# kbdctrl.net
KiCad netlist of a schematic drawn in EAGLE
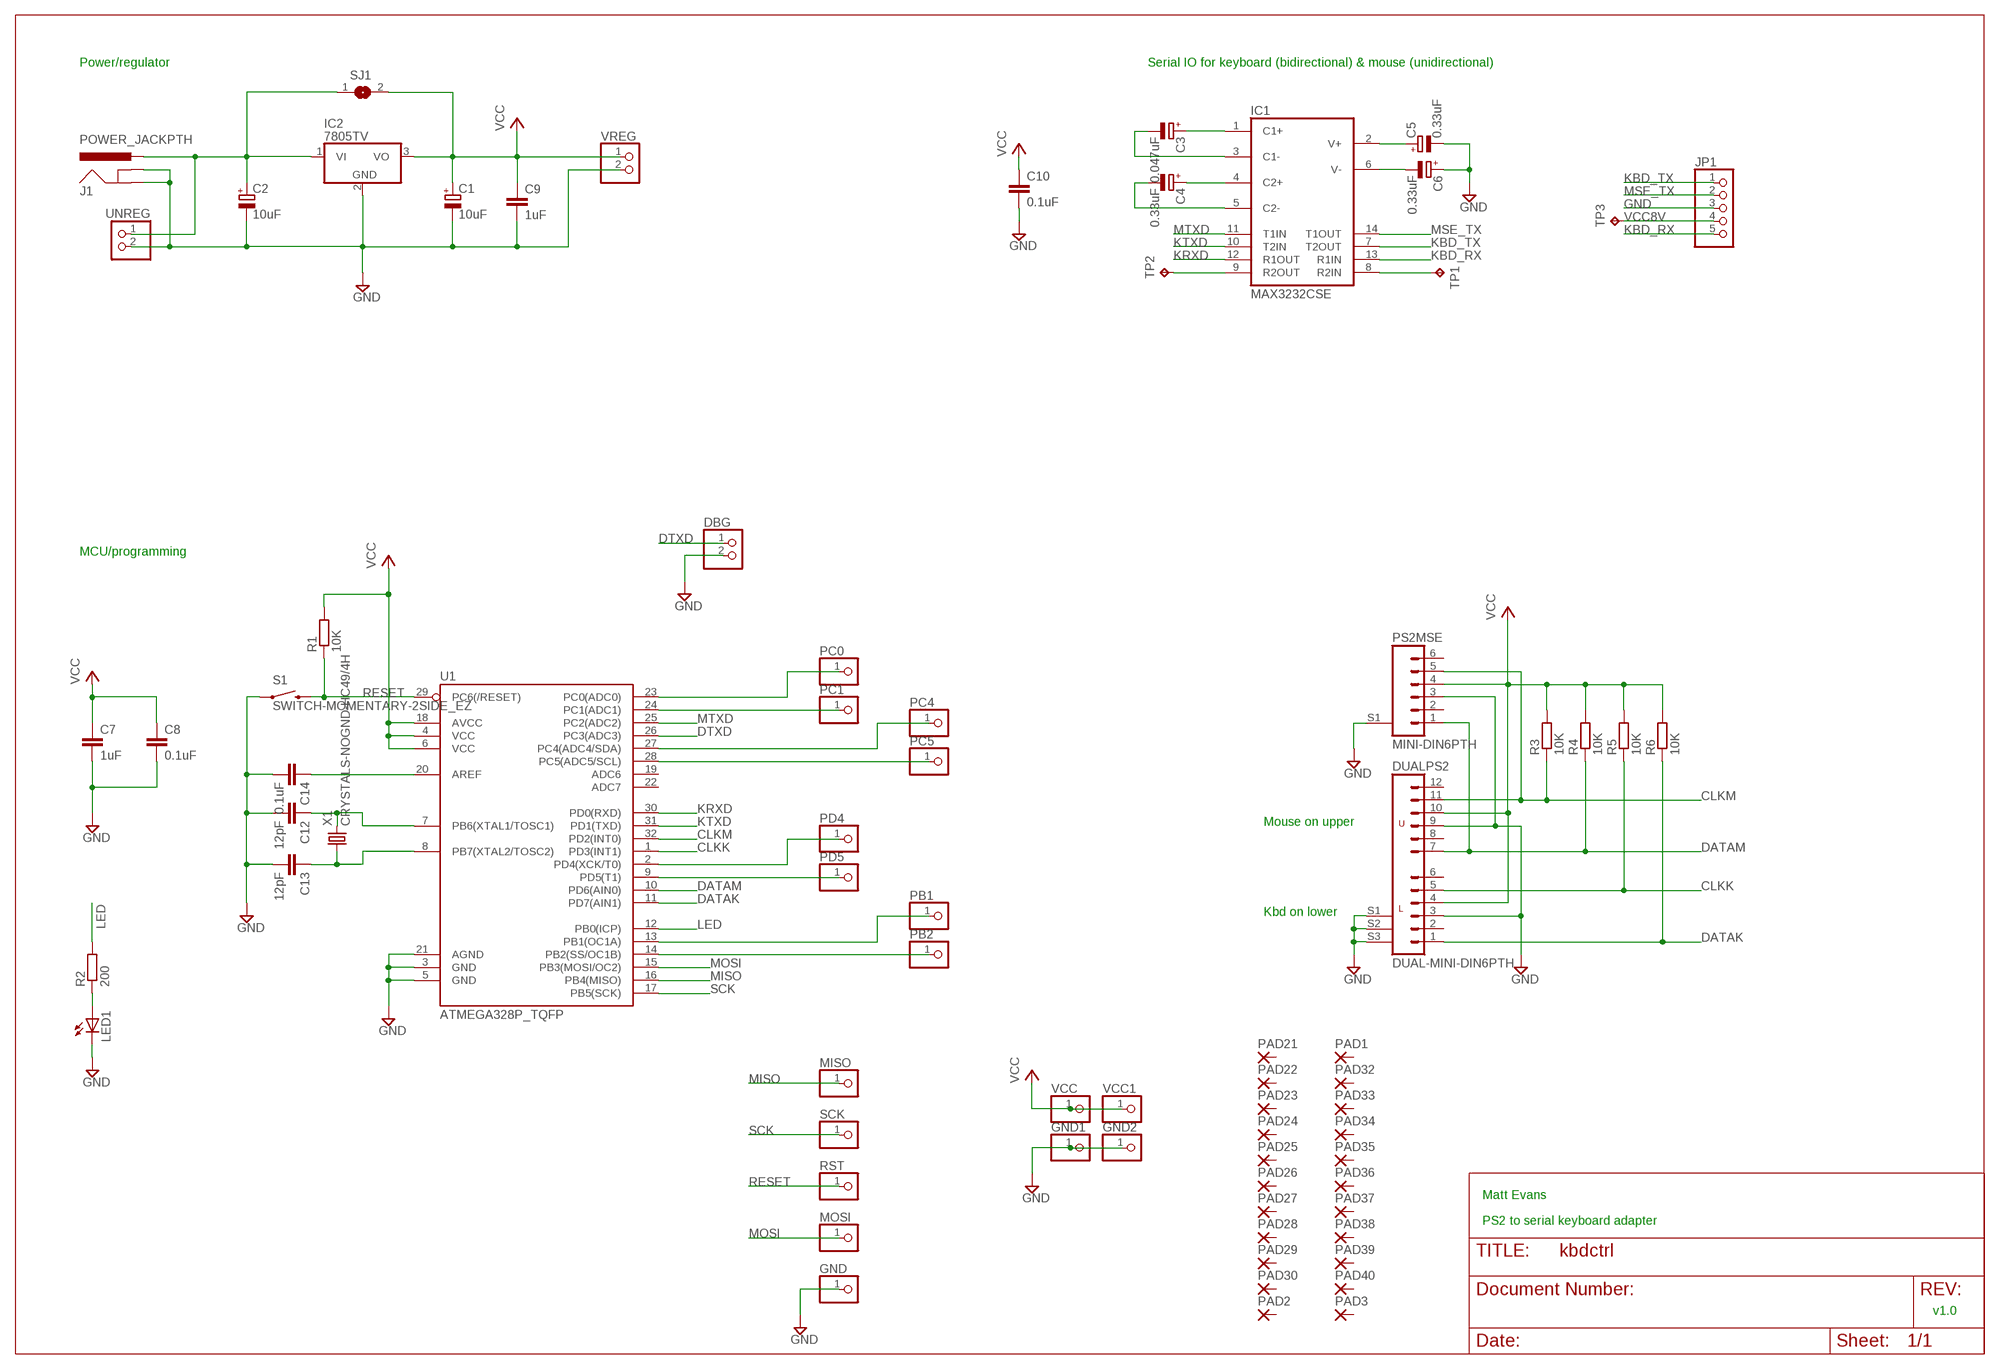
[diagram p0: schematic, sheet 1]

(export (version "E")
  (design (tool "Eeschema 10.0.6"))
  (components
    (comp (ref "C1")
      (value "10uF")
      (footprint "eagle-import:SMC_P")
      (libsource (lib "eagle-import") (part "CPOL-EUSMCP"))
    )
    (comp (ref "C2")
      (value "10uF")
      (footprint "eagle-import:SMC_P")
      (libsource (lib "eagle-import") (part "CPOL-EUSMCP"))
    )
    (comp (ref "C3")
      (value "0.047uF")
      (footprint "eagle-import:SMC_P")
      (libsource (lib "eagle-import") (part "CPOL-EUSMCP"))
    )
    (comp (ref "C4")
      (value "0.33uF")
      (footprint "eagle-import:SMC_P")
      (libsource (lib "eagle-import") (part "CPOL-EUSMCP"))
    )
    (comp (ref "C5")
      (value "0.33uF")
      (footprint "eagle-import:SMC_P")
      (libsource (lib "eagle-import") (part "CPOL-EUSMCP"))
    )
    (comp (ref "C6")
      (value "0.33uF")
      (footprint "eagle-import:SMC_P")
      (libsource (lib "eagle-import") (part "CPOL-EUSMCP"))
    )
    (comp (ref "C7")
      (value "1uF")
      (footprint "eagle-import:C0805")
      (libsource (lib "eagle-import") (part "resistor_C-EUC0805"))
    )
    (comp (ref "C8")
      (value "0.1uF")
      (footprint "eagle-import:C0805")
      (libsource (lib "eagle-import") (part "resistor_C-EUC0805"))
    )
    (comp (ref "C9")
      (value "1uF")
      (footprint "eagle-import:C0805")
      (libsource (lib "eagle-import") (part "resistor_C-EUC0805"))
    )
    (comp (ref "C10")
      (value "0.1uF")
      (footprint "eagle-import:C0805")
      (libsource (lib "eagle-import") (part "resistor_C-EUC0805"))
    )
    (comp (ref "C12")
      (value "12pF")
      (footprint "eagle-import:C0603")
      (libsource (lib "eagle-import") (part "C-EUC0603"))
    )
    (comp (ref "C13")
      (value "12pF")
      (footprint "eagle-import:C0603")
      (libsource (lib "eagle-import") (part "C-EUC0603"))
    )
    (comp (ref "C14")
      (value "0.1uF")
      (footprint "eagle-import:C0603")
      (libsource (lib "eagle-import") (part "C-EUC0603"))
    )
    (comp (ref "DBG")
      (value "PINHD-1X2")
      (footprint "eagle-import:1X02")
      (libsource (lib "eagle-import") (part "PINHD-1X2"))
    )
    (comp (ref "DUALPS2")
      (value "DUAL-MINI-DIN6PTH")
      (footprint "eagle-import:DUAL-MINI-DIN6")
      (libsource (lib "eagle-import") (part "DUAL-MINI-DIN6PTH"))
    )
    (comp (ref "GND")
      (value "PINHD-1X1")
      (footprint "eagle-import:1X01")
      (libsource (lib "eagle-import") (part "PINHD-1X1"))
    )
    (comp (ref "GND1")
      (value "PINHD-1X1")
      (footprint "eagle-import:1X01")
      (libsource (lib "eagle-import") (part "PINHD-1X1"))
    )
    (comp (ref "GND2")
      (value "PINHD-1X1")
      (footprint "eagle-import:1X01")
      (libsource (lib "eagle-import") (part "PINHD-1X1"))
    )
    (comp (ref "IC1")
      (value "MAX3232CSE")
      (footprint "eagle-import:SO16")
      (libsource (lib "eagle-import") (part "MAX3232SEC"))
    )
    (comp (ref "IC2")
      (value "7805TV")
      (footprint "eagle-import:TO220V")
      (libsource (lib "eagle-import") (part "78TV05"))
    )
    (comp (ref "J1")
      (value "POWER_JACKPTH")
      (footprint "eagle-import:POWER_JACK_PTH")
      (libsource (lib "eagle-import") (part "POWER_JACKPTH"))
    )
    (comp (ref "JP1")
      (value "PINHD-1X5")
      (footprint "eagle-import:1X05")
      (libsource (lib "eagle-import") (part "PINHD-1X5"))
    )
    (comp (ref "LED1")
      (value "LEDSML0805")
      (footprint "eagle-import:SML0805")
      (libsource (lib "eagle-import") (part "LEDSML0805"))
    )
    (comp (ref "MISO")
      (value "PINHD-1X1")
      (footprint "eagle-import:1X01")
      (libsource (lib "eagle-import") (part "PINHD-1X1"))
    )
    (comp (ref "MOSI")
      (value "PINHD-1X1")
      (footprint "eagle-import:1X01")
      (libsource (lib "eagle-import") (part "PINHD-1X1"))
    )
    (comp (ref "PAD1")
      (value "1,6/0,9")
      (footprint "eagle-import:1,6_0,9")
      (libsource (lib "eagle-import") (part "1,6/0,9"))
    )
    (comp (ref "PAD2")
      (value "1,6/0,9")
      (footprint "eagle-import:1,6_0,9")
      (libsource (lib "eagle-import") (part "1,6/0,9"))
    )
    (comp (ref "PAD3")
      (value "1,6/0,9")
      (footprint "eagle-import:1,6_0,9")
      (libsource (lib "eagle-import") (part "1,6/0,9"))
    )
    (comp (ref "PAD21")
      (value "1,6/0,9")
      (footprint "eagle-import:1,6_0,9")
      (libsource (lib "eagle-import") (part "1,6/0,9"))
    )
    (comp (ref "PAD22")
      (value "1,6/0,9")
      (footprint "eagle-import:1,6_0,9")
      (libsource (lib "eagle-import") (part "1,6/0,9"))
    )
    (comp (ref "PAD23")
      (value "1,6/0,9")
      (footprint "eagle-import:1,6_0,9")
      (libsource (lib "eagle-import") (part "1,6/0,9"))
    )
    (comp (ref "PAD24")
      (value "1,6/0,9")
      (footprint "eagle-import:1,6_0,9")
      (libsource (lib "eagle-import") (part "1,6/0,9"))
    )
    (comp (ref "PAD25")
      (value "1,6/0,9")
      (footprint "eagle-import:1,6_0,9")
      (libsource (lib "eagle-import") (part "1,6/0,9"))
    )
    (comp (ref "PAD26")
      (value "1,6/0,9")
      (footprint "eagle-import:1,6_0,9")
      (libsource (lib "eagle-import") (part "1,6/0,9"))
    )
    (comp (ref "PAD27")
      (value "1,6/0,9")
      (footprint "eagle-import:1,6_0,9")
      (libsource (lib "eagle-import") (part "1,6/0,9"))
    )
    (comp (ref "PAD28")
      (value "1,6/0,9")
      (footprint "eagle-import:1,6_0,9")
      (libsource (lib "eagle-import") (part "1,6/0,9"))
    )
    (comp (ref "PAD29")
      (value "1,6/0,9")
      (footprint "eagle-import:1,6_0,9")
      (libsource (lib "eagle-import") (part "1,6/0,9"))
    )
    (comp (ref "PAD30")
      (value "1,6/0,9")
      (footprint "eagle-import:1,6_0,9")
      (libsource (lib "eagle-import") (part "1,6/0,9"))
    )
    (comp (ref "PAD32")
      (value "1,6/0,9")
      (footprint "eagle-import:1,6_0,9")
      (libsource (lib "eagle-import") (part "1,6/0,9"))
    )
    (comp (ref "PAD33")
      (value "1,6/0,9")
      (footprint "eagle-import:1,6_0,9")
      (libsource (lib "eagle-import") (part "1,6/0,9"))
    )
    (comp (ref "PAD34")
      (value "1,6/0,9")
      (footprint "eagle-import:1,6_0,9")
      (libsource (lib "eagle-import") (part "1,6/0,9"))
    )
    (comp (ref "PAD35")
      (value "1,6/0,9")
      (footprint "eagle-import:1,6_0,9")
      (libsource (lib "eagle-import") (part "1,6/0,9"))
    )
    (comp (ref "PAD36")
      (value "1,6/0,9")
      (footprint "eagle-import:1,6_0,9")
      (libsource (lib "eagle-import") (part "1,6/0,9"))
    )
    (comp (ref "PAD37")
      (value "1,6/0,9")
      (footprint "eagle-import:1,6_0,9")
      (libsource (lib "eagle-import") (part "1,6/0,9"))
    )
    (comp (ref "PAD38")
      (value "1,6/0,9")
      (footprint "eagle-import:1,6_0,9")
      (libsource (lib "eagle-import") (part "1,6/0,9"))
    )
    (comp (ref "PAD39")
      (value "1,6/0,9")
      (footprint "eagle-import:1,6_0,9")
      (libsource (lib "eagle-import") (part "1,6/0,9"))
    )
    (comp (ref "PAD40")
      (value "1,6/0,9")
      (footprint "eagle-import:1,6_0,9")
      (libsource (lib "eagle-import") (part "1,6/0,9"))
    )
    (comp (ref "PB1")
      (value "PINHD-1X1")
      (footprint "eagle-import:1X01")
      (libsource (lib "eagle-import") (part "PINHD-1X1"))
    )
    (comp (ref "PB2")
      (value "PINHD-1X1")
      (footprint "eagle-import:1X01")
      (libsource (lib "eagle-import") (part "PINHD-1X1"))
    )
    (comp (ref "PC0")
      (value "PINHD-1X1")
      (footprint "eagle-import:1X01")
      (libsource (lib "eagle-import") (part "PINHD-1X1"))
    )
    (comp (ref "PC1")
      (value "PINHD-1X1")
      (footprint "eagle-import:1X01")
      (libsource (lib "eagle-import") (part "PINHD-1X1"))
    )
    (comp (ref "PC4")
      (value "PINHD-1X1")
      (footprint "eagle-import:1X01")
      (libsource (lib "eagle-import") (part "PINHD-1X1"))
    )
    (comp (ref "PC5")
      (value "PINHD-1X1")
      (footprint "eagle-import:1X01")
      (libsource (lib "eagle-import") (part "PINHD-1X1"))
    )
    (comp (ref "PD4")
      (value "PINHD-1X1")
      (footprint "eagle-import:1X01")
      (libsource (lib "eagle-import") (part "PINHD-1X1"))
    )
    (comp (ref "PD5")
      (value "PINHD-1X1")
      (footprint "eagle-import:1X01")
      (libsource (lib "eagle-import") (part "PINHD-1X1"))
    )
    (comp (ref "PS2MSE")
      (value "MINI-DIN6PTH")
      (footprint "eagle-import:MINI-DIN6")
      (libsource (lib "eagle-import") (part "MINI-DIN6PTH"))
    )
    (comp (ref "R1")
      (value "10K")
      (footprint "eagle-import:R0603")
      (libsource (lib "eagle-import") (part "R-EU_R0603"))
    )
    (comp (ref "R2")
      (value "200")
      (footprint "eagle-import:R0603")
      (libsource (lib "eagle-import") (part "R-EU_R0603"))
    )
    (comp (ref "R3")
      (value "10K")
      (footprint "eagle-import:R0603")
      (libsource (lib "eagle-import") (part "R-EU_R0603"))
    )
    (comp (ref "R4")
      (value "10K")
      (footprint "eagle-import:R0603")
      (libsource (lib "eagle-import") (part "R-EU_R0603"))
    )
    (comp (ref "R5")
      (value "10K")
      (footprint "eagle-import:R0603")
      (libsource (lib "eagle-import") (part "R-EU_R0603"))
    )
    (comp (ref "R6")
      (value "10K")
      (footprint "eagle-import:R0603")
      (libsource (lib "eagle-import") (part "R-EU_R0603"))
    )
    (comp (ref "RST")
      (value "PINHD-1X1")
      (footprint "eagle-import:1X01")
      (libsource (lib "eagle-import") (part "PINHD-1X1"))
    )
    (comp (ref "S1")
      (value "SWITCH-MOMENTARY-2SIDE_EZ")
      (footprint "eagle-import:TACTILE-PTH-SIDEEZ")
      (libsource (lib "eagle-import") (part "SWITCH-MOMENTARY-2SIDE_EZ"))
    )
    (comp (ref "SCK")
      (value "PINHD-1X1")
      (footprint "eagle-import:1X01")
      (libsource (lib "eagle-import") (part "PINHD-1X1"))
    )
    (comp (ref "SJ1") (value "SJ") (footprint "eagle-import:SJ") (libsource (lib "eagle-import") (part "SJ")))
    (comp (ref "TP1")
      (value "TPTP09SQ")
      (footprint "eagle-import:TP09SQ")
      (libsource (lib "eagle-import") (part "TPTP09SQ"))
    )
    (comp (ref "TP2")
      (value "TPTP09SQ")
      (footprint "eagle-import:TP09SQ")
      (libsource (lib "eagle-import") (part "TPTP09SQ"))
    )
    (comp (ref "TP3")
      (value "TPTP09SQ")
      (footprint "eagle-import:TP09SQ")
      (libsource (lib "eagle-import") (part "TPTP09SQ"))
    )
    (comp (ref "U1")
      (value "ATMEGA328P_TQFP")
      (footprint "eagle-import:TQFP32-08")
      (libsource (lib "eagle-import") (part "ATMEGA328P_TQFP"))
    )
    (comp (ref "UNREG")
      (value "PINHD-1X2")
      (footprint "eagle-import:1X02")
      (libsource (lib "eagle-import") (part "PINHD-1X2"))
    )
    (comp (ref "VCC")
      (value "PINHD-1X1")
      (footprint "eagle-import:1X01")
      (libsource (lib "eagle-import") (part "PINHD-1X1"))
    )
    (comp (ref "VCC1")
      (value "PINHD-1X1")
      (footprint "eagle-import:1X01")
      (libsource (lib "eagle-import") (part "PINHD-1X1"))
    )
    (comp (ref "VREG")
      (value "PINHD-1X2")
      (footprint "eagle-import:1X02")
      (libsource (lib "eagle-import") (part "PINHD-1X2"))
    )
    (comp (ref "X1")
      (value "CRYSTALS-NOGND-HC49/4H")
      (footprint "eagle-import:HC49")
      (libsource (lib "eagle-import") (part "CRYSTALS-NOGND-HC49/4H"))
    )
  )
  (nets
    (net (code "1") (name "/CLKK") (class "Default")
      (node (ref "DUALPS2") (pin "5") (pinfunction "5_5") (pintype "passive"))
      (node (ref "R5") (pin "1") (pinfunction "1_1") (pintype "passive"))
      (node (ref "U1") (pin "1") (pinfunction "PD3(INT1)_1") (pintype "bidirectional"))
    )
    (net (code "2") (name "/CLKM") (class "Default")
      (node (ref "DUALPS2") (pin "11") (pinfunction "11_11") (pintype "passive"))
      (node (ref "PS2MSE") (pin "5") (pinfunction "5_5") (pintype "passive"))
      (node (ref "R3") (pin "1") (pinfunction "1_1") (pintype "passive"))
      (node (ref "U1") (pin "32") (pinfunction "PD2(INT0)_32") (pintype "bidirectional"))
    )
    (net (code "3") (name "/DATAK") (class "Default")
      (node (ref "DUALPS2") (pin "1") (pinfunction "1_1") (pintype "passive"))
      (node (ref "R6") (pin "1") (pinfunction "1_1") (pintype "passive"))
      (node (ref "U1") (pin "11") (pinfunction "PD7(AIN1)_11") (pintype "bidirectional"))
    )
    (net (code "4") (name "/DATAM") (class "Default")
      (node (ref "DUALPS2") (pin "7") (pinfunction "7_7") (pintype "passive"))
      (node (ref "PS2MSE") (pin "1") (pinfunction "1_1") (pintype "passive"))
      (node (ref "R4") (pin "1") (pinfunction "1_1") (pintype "passive"))
      (node (ref "U1") (pin "10") (pinfunction "PD6(AIN0)_10") (pintype "bidirectional"))
    )
    (net (code "5") (name "/DTXD") (class "Default")
      (node (ref "DBG") (pin "1") (pinfunction "1_1") (pintype "passive"))
      (node (ref "U1") (pin "26") (pinfunction "PC3(ADC3)_26") (pintype "bidirectional"))
    )
    (net (code "6") (name "/KBD_RX") (class "Default")
      (node (ref "IC1") (pin "13") (pinfunction "R1IN_13") (pintype "input"))
      (node (ref "JP1") (pin "5") (pinfunction "5_5") (pintype "passive"))
    )
    (net (code "7") (name "/KBD_TX") (class "Default")
      (node (ref "IC1") (pin "7") (pinfunction "T2OUT_7") (pintype "output"))
      (node (ref "JP1") (pin "1") (pinfunction "1_1") (pintype "passive"))
    )
    (net (code "8") (name "/KRXD") (class "Default")
      (node (ref "IC1") (pin "12") (pinfunction "R1OUT_12") (pintype "output"))
      (node (ref "U1") (pin "30") (pinfunction "PD0(RXD)_30") (pintype "bidirectional"))
    )
    (net (code "9") (name "/KTXD") (class "Default")
      (node (ref "IC1") (pin "10") (pinfunction "T2IN_10") (pintype "input"))
      (node (ref "U1") (pin "31") (pinfunction "PD1(TXD)_31") (pintype "bidirectional"))
    )
    (net (code "10") (name "/LED") (class "Default")
      (node (ref "R2") (pin "2") (pinfunction "2_2") (pintype "passive"))
      (node (ref "U1") (pin "12") (pinfunction "PB0(ICP)_12") (pintype "bidirectional"))
    )
    (net (code "11") (name "/MISO") (class "Default")
      (node (ref "MISO") (pin "1") (pinfunction "1_1") (pintype "passive"))
      (node (ref "U1") (pin "16") (pinfunction "PB4(MISO)_16") (pintype "bidirectional"))
    )
    (net (code "12") (name "/MOSI") (class "Default")
      (node (ref "MOSI") (pin "1") (pinfunction "1_1") (pintype "passive"))
      (node (ref "U1") (pin "15") (pinfunction "PB3(MOSI/OC2)_15") (pintype "bidirectional"))
    )
    (net (code "13") (name "/MSE_TX") (class "Default")
      (node (ref "IC1") (pin "14") (pinfunction "T1OUT_14") (pintype "output"))
      (node (ref "JP1") (pin "2") (pinfunction "2_2") (pintype "passive"))
    )
    (net (code "14") (name "/MTXD") (class "Default")
      (node (ref "IC1") (pin "11") (pinfunction "T1IN_11") (pintype "input"))
      (node (ref "U1") (pin "25") (pinfunction "PC2(ADC2)_25") (pintype "bidirectional"))
    )
    (net (code "15") (name "/RESET") (class "Default")
      (node (ref "R1") (pin "1") (pinfunction "1_1") (pintype "passive"))
      (node (ref "RST") (pin "1") (pinfunction "1_1") (pintype "passive"))
      (node (ref "S1") (pin "2") (pinfunction "2_2") (pintype "passive"))
      (node (ref "U1") (pin "29") (pinfunction "PC6(/RESET)_29") (pintype "bidirectional"))
    )
    (net (code "16") (name "/SCK") (class "Default")
      (node (ref "SCK") (pin "1") (pinfunction "1_1") (pintype "passive"))
      (node (ref "U1") (pin "17") (pinfunction "PB5(SCK)_17") (pintype "bidirectional"))
    )
    (net (code "17") (name "/VCC8V") (class "Default")
      (node (ref "JP1") (pin "4") (pinfunction "4_4") (pintype "passive"))
      (node (ref "TP3") (pin "TP") (pinfunction "TP_TP") (pintype "input"))
    )
    (net (code "18") (name "GND") (class "Default")
      (node (ref "C1") (pin "-") (pinfunction "-_-") (pintype "passive"))
      (node (ref "C10") (pin "2") (pinfunction "2_2") (pintype "passive"))
      (node (ref "C12") (pin "2") (pinfunction "2_2") (pintype "passive"))
      (node (ref "C13") (pin "2") (pinfunction "2_2") (pintype "passive"))
      (node (ref "C14") (pin "2") (pinfunction "2_2") (pintype "passive"))
      (node (ref "C2") (pin "-") (pinfunction "-_-") (pintype "passive"))
      (node (ref "C5") (pin "-") (pinfunction "-_-") (pintype "passive"))
      (node (ref "C6") (pin "+") (pinfunction "+_+") (pintype "passive"))
      (node (ref "C7") (pin "2") (pinfunction "2_2") (pintype "passive"))
      (node (ref "C8") (pin "2") (pinfunction "2_2") (pintype "passive"))
      (node (ref "C9") (pin "2") (pinfunction "2_2") (pintype "passive"))
      (node (ref "DBG") (pin "2") (pinfunction "2_2") (pintype "passive"))
      (node (ref "DUALPS2") (pin "3") (pinfunction "3_3") (pintype "passive"))
      (node (ref "DUALPS2") (pin "9") (pinfunction "9_9") (pintype "passive"))
      (node (ref "DUALPS2") (pin "S1") (pinfunction "P$1_S1") (pintype "passive"))
      (node (ref "DUALPS2") (pin "S2") (pinfunction "P$2_S2") (pintype "passive"))
      (node (ref "DUALPS2") (pin "S3") (pinfunction "P$3_S3") (pintype "passive"))
      (node (ref "GND") (pin "1") (pinfunction "1_1") (pintype "passive"))
      (node (ref "GND1") (pin "1") (pinfunction "1_1") (pintype "passive"))
      (node (ref "GND2") (pin "1") (pinfunction "1_1") (pintype "passive"))
      (node (ref "IC2") (pin "2") (pinfunction "GND_2") (pintype "passive"))
      (node (ref "J1") (pin "GND") (pinfunction "GND_GND") (pintype "bidirectional"))
      (node (ref "J1") (pin "GNDBREAK") (pinfunction "GNDBREAK_GNDBREAK") (pintype "bidirectional"))
      (node (ref "JP1") (pin "3") (pinfunction "3_3") (pintype "passive"))
      (node (ref "LED1") (pin "C") (pinfunction "C_C") (pintype "passive"))
      (node (ref "PS2MSE") (pin "3") (pinfunction "3_3") (pintype "passive"))
      (node (ref "PS2MSE") (pin "S1") (pinfunction "S1_S1") (pintype "passive"))
      (node (ref "S1") (pin "1") (pinfunction "1_1") (pintype "passive"))
      (node (ref "U1") (pin "21") (pinfunction "AGND_21") (pintype "bidirectional"))
      (node (ref "U1") (pin "3") (pinfunction "GND_3") (pintype "bidirectional"))
      (node (ref "U1") (pin "5") (pinfunction "GND_5") (pintype "bidirectional"))
      (node (ref "UNREG") (pin "2") (pinfunction "2_2") (pintype "passive"))
      (node (ref "VREG") (pin "2") (pinfunction "2_2") (pintype "passive"))
    )
    (net (code "19") (name "Net-(IC1A-C1+)") (class "Default")
      (node (ref "C3") (pin "+") (pinfunction "+_+") (pintype "passive"))
      (node (ref "IC1") (pin "1") (pinfunction "C1+_1") (pintype "bidirectional"))
    )
    (net (code "20") (name "Net-(IC1A-C1-)") (class "Default")
      (node (ref "C3") (pin "-") (pinfunction "-_-") (pintype "passive"))
      (node (ref "IC1") (pin "3") (pinfunction "C1-_3") (pintype "bidirectional"))
    )
    (net (code "21") (name "Net-(IC1A-C2+)") (class "Default")
      (node (ref "C4") (pin "+") (pinfunction "+_+") (pintype "passive"))
      (node (ref "IC1") (pin "4") (pinfunction "C2+_4") (pintype "bidirectional"))
    )
    (net (code "22") (name "Net-(IC1A-C2-)") (class "Default")
      (node (ref "C4") (pin "-") (pinfunction "-_-") (pintype "passive"))
      (node (ref "IC1") (pin "5") (pinfunction "C2-_5") (pintype "bidirectional"))
    )
    (net (code "23") (name "Net-(IC1A-R2IN)") (class "Default")
      (node (ref "IC1") (pin "8") (pinfunction "R2IN_8") (pintype "input"))
      (node (ref "TP1") (pin "TP") (pinfunction "TP_TP") (pintype "input"))
    )
    (net (code "24") (name "Net-(IC1A-R2OUT)") (class "Default")
      (node (ref "IC1") (pin "9") (pinfunction "R2OUT_9") (pintype "output"))
      (node (ref "TP2") (pin "TP") (pinfunction "TP_TP") (pintype "input"))
    )
    (net (code "25") (name "Net-(IC1A-V+)") (class "Default")
      (node (ref "C5") (pin "+") (pinfunction "+_+") (pintype "passive"))
      (node (ref "IC1") (pin "2") (pinfunction "V+_2") (pintype "bidirectional"))
    )
    (net (code "26") (name "Net-(IC1A-V-)") (class "Default")
      (node (ref "C6") (pin "-") (pinfunction "-_-") (pintype "passive"))
      (node (ref "IC1") (pin "6") (pinfunction "V-_6") (pintype "bidirectional"))
    )
    (net (code "27") (name "Net-(IC2-VI)") (class "Default")
      (node (ref "C2") (pin "+") (pinfunction "+_+") (pintype "passive"))
      (node (ref "IC2") (pin "1") (pinfunction "VI_1") (pintype "input"))
      (node (ref "J1") (pin "PWR") (pinfunction "PWR_PWR") (pintype "bidirectional"))
      (node (ref "SJ1") (pin "1") (pinfunction "1_1") (pintype "passive"))
      (node (ref "UNREG") (pin "1") (pinfunction "1_1") (pintype "passive"))
    )
    (net (code "28") (name "Net-(LED1-PadA)") (class "Default")
      (node (ref "LED1") (pin "A") (pinfunction "A_A") (pintype "passive"))
      (node (ref "R2") (pin "1") (pinfunction "1_1") (pintype "passive"))
    )
    (net (code "29") (name "Net-(U1-AREF)") (class "Default")
      (node (ref "C14") (pin "1") (pinfunction "1_1") (pintype "passive"))
      (node (ref "U1") (pin "20") (pinfunction "AREF_20") (pintype "bidirectional"))
    )
    (net (code "30") (name "Net-(U1-PB1(OC1A))") (class "Default")
      (node (ref "PB1") (pin "1") (pinfunction "1_1") (pintype "passive"))
      (node (ref "U1") (pin "13") (pinfunction "PB1(OC1A)_13") (pintype "bidirectional"))
    )
    (net (code "31") (name "Net-(U1-PB2(SS{slash}OC1B))") (class "Default")
      (node (ref "PB2") (pin "1") (pinfunction "1_1") (pintype "passive"))
      (node (ref "U1") (pin "14") (pinfunction "PB2(SS/OC1B)_14") (pintype "bidirectional"))
    )
    (net (code "32") (name "Net-(U1-PB6(XTAL1{slash}TOSC1))") (class "Default")
      (node (ref "C12") (pin "1") (pinfunction "1_1") (pintype "passive"))
      (node (ref "U1") (pin "7") (pinfunction "PB6(XTAL1/TOSC1)_7") (pintype "bidirectional"))
      (node (ref "X1") (pin "2") (pinfunction "2_2") (pintype "passive"))
    )
    (net (code "33") (name "Net-(U1-PB7(XTAL2{slash}TOSC2))") (class "Default")
      (node (ref "C13") (pin "1") (pinfunction "1_1") (pintype "passive"))
      (node (ref "U1") (pin "8") (pinfunction "PB7(XTAL2/TOSC2)_8") (pintype "bidirectional"))
      (node (ref "X1") (pin "1") (pinfunction "1_1") (pintype "passive"))
    )
    (net (code "34") (name "Net-(U1-PC0(ADC0))") (class "Default")
      (node (ref "PC0") (pin "1") (pinfunction "1_1") (pintype "passive"))
      (node (ref "U1") (pin "23") (pinfunction "PC0(ADC0)_23") (pintype "bidirectional"))
    )
    (net (code "35") (name "Net-(U1-PC1(ADC1))") (class "Default")
      (node (ref "PC1") (pin "1") (pinfunction "1_1") (pintype "passive"))
      (node (ref "U1") (pin "24") (pinfunction "PC1(ADC1)_24") (pintype "bidirectional"))
    )
    (net (code "36") (name "Net-(U1-PC4(ADC4{slash}SDA))") (class "Default")
      (node (ref "PC4") (pin "1") (pinfunction "1_1") (pintype "passive"))
      (node (ref "U1") (pin "27") (pinfunction "PC4(ADC4/SDA)_27") (pintype "bidirectional"))
    )
    (net (code "37") (name "Net-(U1-PC5(ADC5{slash}SCL))") (class "Default")
      (node (ref "PC5") (pin "1") (pinfunction "1_1") (pintype "passive"))
      (node (ref "U1") (pin "28") (pinfunction "PC5(ADC5/SCL)_28") (pintype "bidirectional"))
    )
    (net (code "38") (name "Net-(U1-PD4(XCK{slash}T0))") (class "Default")
      (node (ref "PD4") (pin "1") (pinfunction "1_1") (pintype "passive"))
      (node (ref "U1") (pin "2") (pinfunction "PD4(XCK/T0)_2") (pintype "bidirectional"))
    )
    (net (code "39") (name "Net-(U1-PD5(T1))") (class "Default")
      (node (ref "PD5") (pin "1") (pinfunction "1_1") (pintype "passive"))
      (node (ref "U1") (pin "9") (pinfunction "PD5(T1)_9") (pintype "bidirectional"))
    )
    (net (code "40") (name "VCC") (class "Default")
      (node (ref "C1") (pin "+") (pinfunction "+_+") (pintype "passive"))
      (node (ref "C10") (pin "1") (pinfunction "1_1") (pintype "passive"))
      (node (ref "C7") (pin "1") (pinfunction "1_1") (pintype "passive"))
      (node (ref "C8") (pin "1") (pinfunction "1_1") (pintype "passive"))
      (node (ref "C9") (pin "1") (pinfunction "1_1") (pintype "passive"))
      (node (ref "DUALPS2") (pin "10") (pinfunction "10_10") (pintype "passive"))
      (node (ref "DUALPS2") (pin "4") (pinfunction "4_4") (pintype "passive"))
      (node (ref "IC2") (pin "3") (pinfunction "VO_3") (pintype "passive"))
      (node (ref "PS2MSE") (pin "4") (pinfunction "4_4") (pintype "passive"))
      (node (ref "R1") (pin "2") (pinfunction "2_2") (pintype "passive"))
      (node (ref "R3") (pin "2") (pinfunction "2_2") (pintype "passive"))
      (node (ref "R4") (pin "2") (pinfunction "2_2") (pintype "passive"))
      (node (ref "R5") (pin "2") (pinfunction "2_2") (pintype "passive"))
      (node (ref "R6") (pin "2") (pinfunction "2_2") (pintype "passive"))
      (node (ref "SJ1") (pin "2") (pinfunction "2_2") (pintype "passive"))
      (node (ref "U1") (pin "18") (pinfunction "AVCC_18") (pintype "bidirectional"))
      (node (ref "U1") (pin "4") (pinfunction "VCC_4") (pintype "bidirectional"))
      (node (ref "U1") (pin "6") (pinfunction "VCC_6") (pintype "bidirectional"))
      (node (ref "VCC") (pin "1") (pinfunction "1_1") (pintype "passive"))
      (node (ref "VCC1") (pin "1") (pinfunction "1_1") (pintype "passive"))
      (node (ref "VREG") (pin "1") (pinfunction "1_1") (pintype "passive"))
    )
    (net (code "41") (name "unconnected-(DUALPS2-Pad2)") (class "Default")
      (node (ref "DUALPS2") (pin "2") (pinfunction "2_2") (pintype "passive"))
    )
    (net (code "42") (name "unconnected-(DUALPS2-Pad6)") (class "Default")
      (node (ref "DUALPS2") (pin "6") (pinfunction "6_6") (pintype "passive"))
    )
    (net (code "43") (name "unconnected-(DUALPS2-Pad8)") (class "Default")
      (node (ref "DUALPS2") (pin "8") (pinfunction "8_8") (pintype "passive"))
    )
    (net (code "44") (name "unconnected-(DUALPS2-Pad12)") (class "Default")
      (node (ref "DUALPS2") (pin "12") (pinfunction "12_12") (pintype "passive"))
    )
    (net (code "45") (name "unconnected-(PAD1-P-Pad1)") (class "Default")
      (node (ref "PAD1") (pin "1") (pinfunction "P_1") (pintype "passive"))
    )
    (net (code "46") (name "unconnected-(PAD2-P-Pad1)") (class "Default")
      (node (ref "PAD2") (pin "1") (pinfunction "P_1") (pintype "passive"))
    )
    (net (code "47") (name "unconnected-(PAD3-P-Pad1)") (class "Default")
      (node (ref "PAD3") (pin "1") (pinfunction "P_1") (pintype "passive"))
    )
    (net (code "48") (name "unconnected-(PAD21-P-Pad1)") (class "Default")
      (node (ref "PAD21") (pin "1") (pinfunction "P_1") (pintype "passive"))
    )
    (net (code "49") (name "unconnected-(PAD22-P-Pad1)") (class "Default")
      (node (ref "PAD22") (pin "1") (pinfunction "P_1") (pintype "passive"))
    )
    (net (code "50") (name "unconnected-(PAD23-P-Pad1)") (class "Default")
      (node (ref "PAD23") (pin "1") (pinfunction "P_1") (pintype "passive"))
    )
    (net (code "51") (name "unconnected-(PAD24-P-Pad1)") (class "Default")
      (node (ref "PAD24") (pin "1") (pinfunction "P_1") (pintype "passive"))
    )
    (net (code "52") (name "unconnected-(PAD25-P-Pad1)") (class "Default")
      (node (ref "PAD25") (pin "1") (pinfunction "P_1") (pintype "passive"))
    )
    (net (code "53") (name "unconnected-(PAD26-P-Pad1)") (class "Default")
      (node (ref "PAD26") (pin "1") (pinfunction "P_1") (pintype "passive"))
    )
    (net (code "54") (name "unconnected-(PAD27-P-Pad1)") (class "Default")
      (node (ref "PAD27") (pin "1") (pinfunction "P_1") (pintype "passive"))
    )
    (net (code "55") (name "unconnected-(PAD28-P-Pad1)") (class "Default")
      (node (ref "PAD28") (pin "1") (pinfunction "P_1") (pintype "passive"))
    )
    (net (code "56") (name "unconnected-(PAD29-P-Pad1)") (class "Default")
      (node (ref "PAD29") (pin "1") (pinfunction "P_1") (pintype "passive"))
    )
    (net (code "57") (name "unconnected-(PAD30-P-Pad1)") (class "Default")
      (node (ref "PAD30") (pin "1") (pinfunction "P_1") (pintype "passive"))
    )
    (net (code "58") (name "unconnected-(PAD32-P-Pad1)") (class "Default")
      (node (ref "PAD32") (pin "1") (pinfunction "P_1") (pintype "passive"))
    )
    (net (code "59") (name "unconnected-(PAD33-P-Pad1)") (class "Default")
      (node (ref "PAD33") (pin "1") (pinfunction "P_1") (pintype "passive"))
    )
    (net (code "60") (name "unconnected-(PAD34-P-Pad1)") (class "Default")
      (node (ref "PAD34") (pin "1") (pinfunction "P_1") (pintype "passive"))
    )
    (net (code "61") (name "unconnected-(PAD35-P-Pad1)") (class "Default")
      (node (ref "PAD35") (pin "1") (pinfunction "P_1") (pintype "passive"))
    )
    (net (code "62") (name "unconnected-(PAD36-P-Pad1)") (class "Default")
      (node (ref "PAD36") (pin "1") (pinfunction "P_1") (pintype "passive"))
    )
    (net (code "63") (name "unconnected-(PAD37-P-Pad1)") (class "Default")
      (node (ref "PAD37") (pin "1") (pinfunction "P_1") (pintype "passive"))
    )
    (net (code "64") (name "unconnected-(PAD38-P-Pad1)") (class "Default")
      (node (ref "PAD38") (pin "1") (pinfunction "P_1") (pintype "passive"))
    )
    (net (code "65") (name "unconnected-(PAD39-P-Pad1)") (class "Default")
      (node (ref "PAD39") (pin "1") (pinfunction "P_1") (pintype "passive"))
    )
    (net (code "66") (name "unconnected-(PAD40-P-Pad1)") (class "Default")
      (node (ref "PAD40") (pin "1") (pinfunction "P_1") (pintype "passive"))
    )
    (net (code "67") (name "unconnected-(PS2MSE-Pad2)") (class "Default")
      (node (ref "PS2MSE") (pin "2") (pinfunction "2_2") (pintype "passive"))
    )
    (net (code "68") (name "unconnected-(PS2MSE-Pad6)") (class "Default")
      (node (ref "PS2MSE") (pin "6") (pinfunction "6_6") (pintype "passive"))
    )
    (net (code "69") (name "unconnected-(U1-ADC6-Pad19)") (class "Default")
      (node (ref "U1") (pin "19") (pinfunction "ADC6_19") (pintype "bidirectional"))
    )
    (net (code "70") (name "unconnected-(U1-ADC7-Pad22)") (class "Default")
      (node (ref "U1") (pin "22") (pinfunction "ADC7_22") (pintype "bidirectional"))
    )
  )
)
